# design.net
KiCad netlist of a schematic drawn in EAGLE
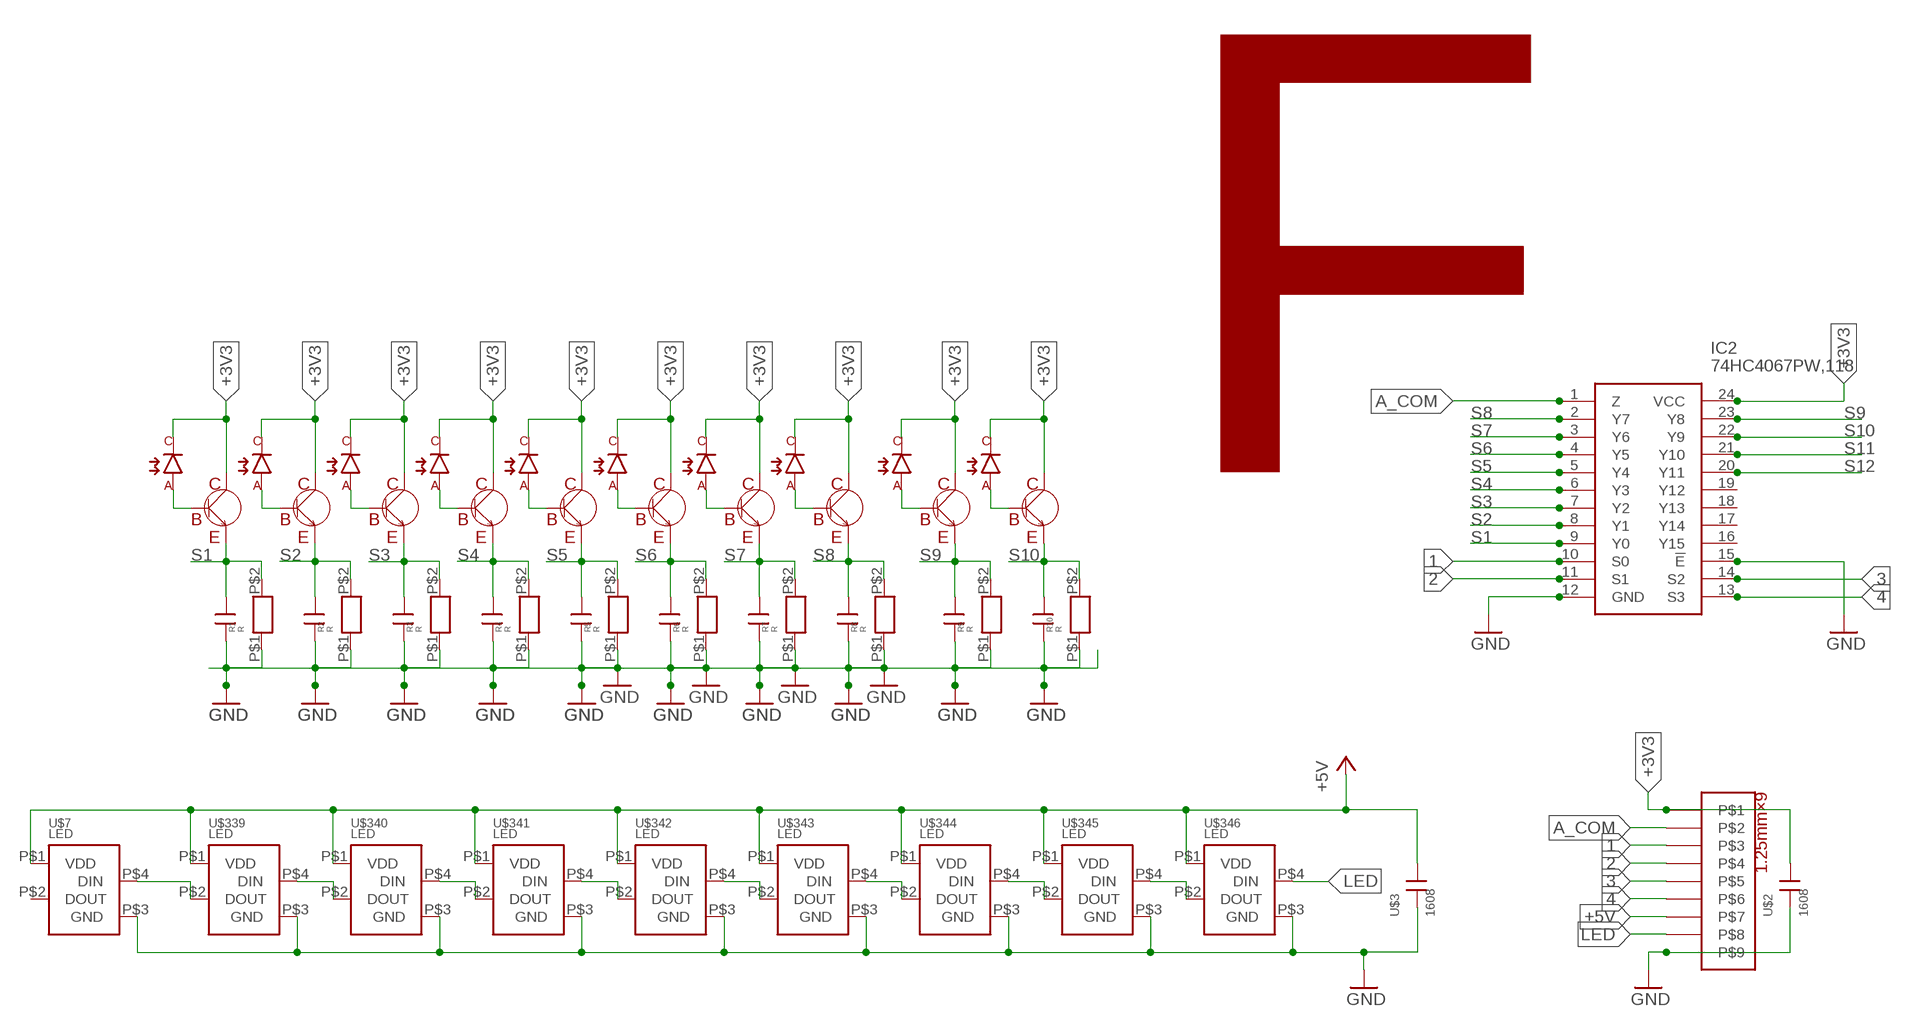
[diagram p0: schematic, sheet 2]

(export (version "E")
  (design (tool "Eeschema 10.0.6"))
  (components
    (comp (ref "C1")
      (value "1608")
      (footprint "eagle-import:CON")
      (libsource (lib "eagle-import") (part "1608"))
    )
    (comp (ref "C2")
      (value "1608")
      (footprint "eagle-import:CON")
      (libsource (lib "eagle-import") (part "1608"))
    )
    (comp (ref "C3")
      (value "1608")
      (footprint "eagle-import:CON")
      (libsource (lib "eagle-import") (part "1608"))
    )
    (comp (ref "C4")
      (value "1608")
      (footprint "eagle-import:CON")
      (libsource (lib "eagle-import") (part "1608"))
    )
    (comp (ref "C5")
      (value "1608")
      (footprint "eagle-import:CON")
      (libsource (lib "eagle-import") (part "1608"))
    )
    (comp (ref "C6")
      (value "1608")
      (footprint "eagle-import:CON")
      (libsource (lib "eagle-import") (part "1608"))
    )
    (comp (ref "C7")
      (value "1608")
      (footprint "eagle-import:CON")
      (libsource (lib "eagle-import") (part "1608"))
    )
    (comp (ref "C8")
      (value "1608")
      (footprint "eagle-import:CON")
      (libsource (lib "eagle-import") (part "1608"))
    )
    (comp (ref "C9")
      (value "1608")
      (footprint "eagle-import:CON")
      (libsource (lib "eagle-import") (part "1608"))
    )
    (comp (ref "C10")
      (value "1608")
      (footprint "eagle-import:CON")
      (libsource (lib "eagle-import") (part "1608"))
    )
    (comp (ref "IC2")
      (value "74HC4067PW,118")
      (footprint "eagle-import:SOP65P640X110-24N")
      (fields (field (name "MOUSER_PART_NUMBER") "771-74HC4067PW-T"))
      (libsource (lib "eagle-import") (part "74HC4067PW,118"))
    )
    (comp (ref "R1") (value "R") (footprint "eagle-import:1608") (libsource (lib "eagle-import") (part "R")))
    (comp (ref "R2") (value "R") (footprint "eagle-import:1608") (libsource (lib "eagle-import") (part "R")))
    (comp (ref "R3") (value "R") (footprint "eagle-import:1608") (libsource (lib "eagle-import") (part "R")))
    (comp (ref "R4") (value "R") (footprint "eagle-import:1608") (libsource (lib "eagle-import") (part "R")))
    (comp (ref "R5") (value "R") (footprint "eagle-import:1608") (libsource (lib "eagle-import") (part "R")))
    (comp (ref "R6") (value "R") (footprint "eagle-import:1608") (libsource (lib "eagle-import") (part "R")))
    (comp (ref "R7") (value "R") (footprint "eagle-import:1608") (libsource (lib "eagle-import") (part "R")))
    (comp (ref "R8") (value "R") (footprint "eagle-import:1608") (libsource (lib "eagle-import") (part "R")))
    (comp (ref "R9") (value "R") (footprint "eagle-import:1608") (libsource (lib "eagle-import") (part "R")))
    (comp (ref "R10") (value "R") (footprint "eagle-import:1608") (libsource (lib "eagle-import") (part "R")))
    (comp (ref "U$1")
      (value "1MMCON")
      (footprint "eagle-import:1MMCON")
      (libsource (lib "eagle-import") (part "1MMCON"))
    )
    (comp (ref "U$2")
      (value "1608")
      (footprint "eagle-import:CON")
      (libsource (lib "eagle-import") (part "1608"))
    )
    (comp (ref "U$3")
      (value "1608")
      (footprint "eagle-import:CON")
      (libsource (lib "eagle-import") (part "1608"))
    )
    (comp (ref "U$7")
      (value "LED")
      (footprint "eagle-import:LED")
      (libsource (lib "eagle-import") (part "LED"))
    )
    (comp (ref "U$17")
      (value "2CS2712")
      (footprint "eagle-import:TRANS_SSM3J325F,LF")
      (libsource (lib "eagle-import") (part "2CS2712"))
    )
    (comp (ref "U$18")
      (value "フォトダイオード")
      (footprint "eagle-import:フォトダイオード")
      (libsource (lib "eagle-import") (part "フォトダイオード"))
    )
    (comp (ref "U$19")
      (value "2CS2712")
      (footprint "eagle-import:TRANS_SSM3J325F,LF")
      (libsource (lib "eagle-import") (part "2CS2712"))
    )
    (comp (ref "U$20")
      (value "フォトダイオード")
      (footprint "eagle-import:フォトダイオード")
      (libsource (lib "eagle-import") (part "フォトダイオード"))
    )
    (comp (ref "U$21")
      (value "2CS2712")
      (footprint "eagle-import:TRANS_SSM3J325F,LF")
      (libsource (lib "eagle-import") (part "2CS2712"))
    )
    (comp (ref "U$22")
      (value "フォトダイオード")
      (footprint "eagle-import:フォトダイオード")
      (libsource (lib "eagle-import") (part "フォトダイオード"))
    )
    (comp (ref "U$23")
      (value "2CS2712")
      (footprint "eagle-import:TRANS_SSM3J325F,LF")
      (libsource (lib "eagle-import") (part "2CS2712"))
    )
    (comp (ref "U$24")
      (value "フォトダイオード")
      (footprint "eagle-import:フォトダイオード")
      (libsource (lib "eagle-import") (part "フォトダイオード"))
    )
    (comp (ref "U$25")
      (value "2CS2712")
      (footprint "eagle-import:TRANS_SSM3J325F,LF")
      (libsource (lib "eagle-import") (part "2CS2712"))
    )
    (comp (ref "U$26")
      (value "フォトダイオード")
      (footprint "eagle-import:フォトダイオード")
      (libsource (lib "eagle-import") (part "フォトダイオード"))
    )
    (comp (ref "U$27")
      (value "2CS2712")
      (footprint "eagle-import:TRANS_SSM3J325F,LF")
      (libsource (lib "eagle-import") (part "2CS2712"))
    )
    (comp (ref "U$28")
      (value "フォトダイオード")
      (footprint "eagle-import:フォトダイオード")
      (libsource (lib "eagle-import") (part "フォトダイオード"))
    )
    (comp (ref "U$29")
      (value "2CS2712")
      (footprint "eagle-import:TRANS_SSM3J325F,LF")
      (libsource (lib "eagle-import") (part "2CS2712"))
    )
    (comp (ref "U$30")
      (value "フォトダイオード")
      (footprint "eagle-import:フォトダイオード")
      (libsource (lib "eagle-import") (part "フォトダイオード"))
    )
    (comp (ref "U$31")
      (value "2CS2712")
      (footprint "eagle-import:TRANS_SSM3J325F,LF")
      (libsource (lib "eagle-import") (part "2CS2712"))
    )
    (comp (ref "U$32")
      (value "フォトダイオード")
      (footprint "eagle-import:フォトダイオード")
      (libsource (lib "eagle-import") (part "フォトダイオード"))
    )
    (comp (ref "U$53")
      (value "2CS2712")
      (footprint "eagle-import:TRANS_SSM3J325F,LF")
      (libsource (lib "eagle-import") (part "2CS2712"))
    )
    (comp (ref "U$54")
      (value "フォトダイオード")
      (footprint "eagle-import:フォトダイオード")
      (libsource (lib "eagle-import") (part "フォトダイオード"))
    )
    (comp (ref "U$55")
      (value "2CS2712")
      (footprint "eagle-import:TRANS_SSM3J325F,LF")
      (libsource (lib "eagle-import") (part "2CS2712"))
    )
    (comp (ref "U$56")
      (value "フォトダイオード")
      (footprint "eagle-import:フォトダイオード")
      (libsource (lib "eagle-import") (part "フォトダイオード"))
    )
    (comp (ref "U$339")
      (value "LED")
      (footprint "eagle-import:LED")
      (libsource (lib "eagle-import") (part "LED"))
    )
    (comp (ref "U$340")
      (value "LED")
      (footprint "eagle-import:LED")
      (libsource (lib "eagle-import") (part "LED"))
    )
    (comp (ref "U$341")
      (value "LED")
      (footprint "eagle-import:LED")
      (libsource (lib "eagle-import") (part "LED"))
    )
    (comp (ref "U$342")
      (value "LED")
      (footprint "eagle-import:LED")
      (libsource (lib "eagle-import") (part "LED"))
    )
    (comp (ref "U$343")
      (value "LED")
      (footprint "eagle-import:LED")
      (libsource (lib "eagle-import") (part "LED"))
    )
    (comp (ref "U$344")
      (value "LED")
      (footprint "eagle-import:LED")
      (libsource (lib "eagle-import") (part "LED"))
    )
    (comp (ref "U$345")
      (value "LED")
      (footprint "eagle-import:LED")
      (libsource (lib "eagle-import") (part "LED"))
    )
    (comp (ref "U$346")
      (value "LED")
      (footprint "eagle-import:LED")
      (libsource (lib "eagle-import") (part "LED"))
    )
  )
  (nets
    (net (code "1") (name "+3V3") (class "Default")
      (node (ref "IC2") (pin "24") (pinfunction "VCC_24") (pintype "bidirectional"))
      (node (ref "U$1") (pin "P$1") (pinfunction "P$1_P$1") (pintype "bidirectional"))
      (node (ref "U$17") (pin "C") (pinfunction "C_C") (pintype "bidirectional"))
      (node (ref "U$18") (pin "C") (pinfunction "C_C") (pintype "bidirectional"))
      (node (ref "U$19") (pin "C") (pinfunction "C_C") (pintype "bidirectional"))
      (node (ref "U$2") (pin "P$1") (pinfunction "1_P$1") (pintype "bidirectional"))
      (node (ref "U$20") (pin "C") (pinfunction "C_C") (pintype "bidirectional"))
      (node (ref "U$21") (pin "C") (pinfunction "C_C") (pintype "bidirectional"))
      (node (ref "U$22") (pin "C") (pinfunction "C_C") (pintype "bidirectional"))
      (node (ref "U$23") (pin "C") (pinfunction "C_C") (pintype "bidirectional"))
      (node (ref "U$24") (pin "C") (pinfunction "C_C") (pintype "bidirectional"))
      (node (ref "U$25") (pin "C") (pinfunction "C_C") (pintype "bidirectional"))
      (node (ref "U$26") (pin "C") (pinfunction "C_C") (pintype "bidirectional"))
      (node (ref "U$27") (pin "C") (pinfunction "C_C") (pintype "bidirectional"))
      (node (ref "U$28") (pin "C") (pinfunction "C_C") (pintype "bidirectional"))
      (node (ref "U$29") (pin "C") (pinfunction "C_C") (pintype "bidirectional"))
      (node (ref "U$30") (pin "C") (pinfunction "C_C") (pintype "bidirectional"))
      (node (ref "U$31") (pin "C") (pinfunction "C_C") (pintype "bidirectional"))
      (node (ref "U$32") (pin "C") (pinfunction "C_C") (pintype "bidirectional"))
      (node (ref "U$53") (pin "C") (pinfunction "C_C") (pintype "bidirectional"))
      (node (ref "U$54") (pin "C") (pinfunction "C_C") (pintype "bidirectional"))
      (node (ref "U$55") (pin "C") (pinfunction "C_C") (pintype "bidirectional"))
      (node (ref "U$56") (pin "C") (pinfunction "C_C") (pintype "bidirectional"))
    )
    (net (code "2") (name "+5V") (class "Default")
      (node (ref "U$1") (pin "P$7") (pinfunction "P$7_P$7") (pintype "bidirectional"))
      (node (ref "U$3") (pin "P$1") (pinfunction "1_P$1") (pintype "bidirectional"))
      (node (ref "U$339") (pin "P$1") (pinfunction "VDD_P$1") (pintype "bidirectional"))
      (node (ref "U$340") (pin "P$1") (pinfunction "VDD_P$1") (pintype "bidirectional"))
      (node (ref "U$341") (pin "P$1") (pinfunction "VDD_P$1") (pintype "bidirectional"))
      (node (ref "U$342") (pin "P$1") (pinfunction "VDD_P$1") (pintype "bidirectional"))
      (node (ref "U$343") (pin "P$1") (pinfunction "VDD_P$1") (pintype "bidirectional"))
      (node (ref "U$344") (pin "P$1") (pinfunction "VDD_P$1") (pintype "bidirectional"))
      (node (ref "U$345") (pin "P$1") (pinfunction "VDD_P$1") (pintype "bidirectional"))
      (node (ref "U$346") (pin "P$1") (pinfunction "VDD_P$1") (pintype "bidirectional"))
      (node (ref "U$7") (pin "P$1") (pinfunction "VDD_P$1") (pintype "bidirectional"))
    )
    (net (code "3") (name "1") (class "Default")
      (node (ref "IC2") (pin "10") (pinfunction "S0_10") (pintype "bidirectional"))
      (node (ref "U$1") (pin "P$3") (pinfunction "P$3_P$3") (pintype "bidirectional"))
    )
    (net (code "4") (name "2") (class "Default")
      (node (ref "IC2") (pin "11") (pinfunction "S1_11") (pintype "bidirectional"))
      (node (ref "U$1") (pin "P$4") (pinfunction "P$4_P$4") (pintype "bidirectional"))
    )
    (net (code "5") (name "3") (class "Default")
      (node (ref "IC2") (pin "14") (pinfunction "S2_14") (pintype "bidirectional"))
      (node (ref "U$1") (pin "P$5") (pinfunction "P$5_P$5") (pintype "bidirectional"))
    )
    (net (code "6") (name "4") (class "Default")
      (node (ref "IC2") (pin "13") (pinfunction "S3_13") (pintype "bidirectional"))
      (node (ref "U$1") (pin "P$6") (pinfunction "P$6_P$6") (pintype "bidirectional"))
    )
    (net (code "7") (name "A_COM") (class "Default")
      (node (ref "IC2") (pin "1") (pinfunction "Z_1") (pintype "bidirectional"))
      (node (ref "U$1") (pin "P$2") (pinfunction "P$2_P$2") (pintype "bidirectional"))
    )
    (net (code "8") (name "GND") (class "Default")
      (node (ref "C1") (pin "P$2") (pinfunction "2_P$2") (pintype "bidirectional"))
      (node (ref "C10") (pin "P$2") (pinfunction "2_P$2") (pintype "bidirectional"))
      (node (ref "C2") (pin "P$2") (pinfunction "2_P$2") (pintype "bidirectional"))
      (node (ref "C3") (pin "P$2") (pinfunction "2_P$2") (pintype "bidirectional"))
      (node (ref "C4") (pin "P$2") (pinfunction "2_P$2") (pintype "bidirectional"))
      (node (ref "C5") (pin "P$2") (pinfunction "2_P$2") (pintype "bidirectional"))
      (node (ref "C6") (pin "P$2") (pinfunction "2_P$2") (pintype "bidirectional"))
      (node (ref "C7") (pin "P$2") (pinfunction "2_P$2") (pintype "bidirectional"))
      (node (ref "C8") (pin "P$2") (pinfunction "2_P$2") (pintype "bidirectional"))
      (node (ref "C9") (pin "P$2") (pinfunction "2_P$2") (pintype "bidirectional"))
      (node (ref "IC2") (pin "12") (pinfunction "GND_12") (pintype "bidirectional"))
      (node (ref "IC2") (pin "15") (pinfunction "~{E}_15") (pintype "bidirectional"))
      (node (ref "R1") (pin "P$1") (pinfunction "P$1_P$1") (pintype "bidirectional"))
      (node (ref "R10") (pin "P$1") (pinfunction "P$1_P$1") (pintype "bidirectional"))
      (node (ref "R2") (pin "P$1") (pinfunction "P$1_P$1") (pintype "bidirectional"))
      (node (ref "R3") (pin "P$1") (pinfunction "P$1_P$1") (pintype "bidirectional"))
      (node (ref "R4") (pin "P$1") (pinfunction "P$1_P$1") (pintype "bidirectional"))
      (node (ref "R5") (pin "P$1") (pinfunction "P$1_P$1") (pintype "bidirectional"))
      (node (ref "R6") (pin "P$1") (pinfunction "P$1_P$1") (pintype "bidirectional"))
      (node (ref "R7") (pin "P$1") (pinfunction "P$1_P$1") (pintype "bidirectional"))
      (node (ref "R8") (pin "P$1") (pinfunction "P$1_P$1") (pintype "bidirectional"))
      (node (ref "R9") (pin "P$1") (pinfunction "P$1_P$1") (pintype "bidirectional"))
      (node (ref "U$1") (pin "P$9") (pinfunction "P$9_P$9") (pintype "bidirectional"))
      (node (ref "U$2") (pin "P$2") (pinfunction "2_P$2") (pintype "bidirectional"))
      (node (ref "U$3") (pin "P$2") (pinfunction "2_P$2") (pintype "bidirectional"))
      (node (ref "U$339") (pin "P$3") (pinfunction "GND_P$3") (pintype "bidirectional"))
      (node (ref "U$340") (pin "P$3") (pinfunction "GND_P$3") (pintype "bidirectional"))
      (node (ref "U$341") (pin "P$3") (pinfunction "GND_P$3") (pintype "bidirectional"))
      (node (ref "U$342") (pin "P$3") (pinfunction "GND_P$3") (pintype "bidirectional"))
      (node (ref "U$343") (pin "P$3") (pinfunction "GND_P$3") (pintype "bidirectional"))
      (node (ref "U$344") (pin "P$3") (pinfunction "GND_P$3") (pintype "bidirectional"))
      (node (ref "U$345") (pin "P$3") (pinfunction "GND_P$3") (pintype "bidirectional"))
      (node (ref "U$346") (pin "P$3") (pinfunction "GND_P$3") (pintype "bidirectional"))
      (node (ref "U$7") (pin "P$3") (pinfunction "GND_P$3") (pintype "bidirectional"))
    )
    (net (code "9") (name "LED") (class "Default")
      (node (ref "U$1") (pin "P$8") (pinfunction "P$8_P$8") (pintype "bidirectional"))
      (node (ref "U$346") (pin "P$4") (pinfunction "DIN_P$4") (pintype "bidirectional"))
    )
    (net (code "10") (name "Net-(U$17-PadB)") (class "Default")
      (node (ref "U$17") (pin "B") (pinfunction "B_B") (pintype "bidirectional"))
      (node (ref "U$18") (pin "A") (pinfunction "A_A") (pintype "bidirectional"))
    )
    (net (code "11") (name "Net-(U$19-PadB)") (class "Default")
      (node (ref "U$19") (pin "B") (pinfunction "B_B") (pintype "bidirectional"))
      (node (ref "U$20") (pin "A") (pinfunction "A_A") (pintype "bidirectional"))
    )
    (net (code "12") (name "Net-(U$21-PadB)") (class "Default")
      (node (ref "U$21") (pin "B") (pinfunction "B_B") (pintype "bidirectional"))
      (node (ref "U$22") (pin "A") (pinfunction "A_A") (pintype "bidirectional"))
    )
    (net (code "13") (name "Net-(U$23-PadB)") (class "Default")
      (node (ref "U$23") (pin "B") (pinfunction "B_B") (pintype "bidirectional"))
      (node (ref "U$24") (pin "A") (pinfunction "A_A") (pintype "bidirectional"))
    )
    (net (code "14") (name "Net-(U$25-PadB)") (class "Default")
      (node (ref "U$25") (pin "B") (pinfunction "B_B") (pintype "bidirectional"))
      (node (ref "U$26") (pin "A") (pinfunction "A_A") (pintype "bidirectional"))
    )
    (net (code "15") (name "Net-(U$27-PadB)") (class "Default")
      (node (ref "U$27") (pin "B") (pinfunction "B_B") (pintype "bidirectional"))
      (node (ref "U$28") (pin "A") (pinfunction "A_A") (pintype "bidirectional"))
    )
    (net (code "16") (name "Net-(U$29-PadB)") (class "Default")
      (node (ref "U$29") (pin "B") (pinfunction "B_B") (pintype "bidirectional"))
      (node (ref "U$30") (pin "A") (pinfunction "A_A") (pintype "bidirectional"))
    )
    (net (code "17") (name "Net-(U$31-PadB)") (class "Default")
      (node (ref "U$31") (pin "B") (pinfunction "B_B") (pintype "bidirectional"))
      (node (ref "U$32") (pin "A") (pinfunction "A_A") (pintype "bidirectional"))
    )
    (net (code "18") (name "Net-(U$53-PadB)") (class "Default")
      (node (ref "U$53") (pin "B") (pinfunction "B_B") (pintype "bidirectional"))
      (node (ref "U$54") (pin "A") (pinfunction "A_A") (pintype "bidirectional"))
    )
    (net (code "19") (name "Net-(U$55-PadB)") (class "Default")
      (node (ref "U$55") (pin "B") (pinfunction "B_B") (pintype "bidirectional"))
      (node (ref "U$56") (pin "A") (pinfunction "A_A") (pintype "bidirectional"))
    )
    (net (code "20") (name "Net-(U$339-DIN)") (class "Default")
      (node (ref "U$339") (pin "P$4") (pinfunction "DIN_P$4") (pintype "bidirectional"))
      (node (ref "U$340") (pin "P$2") (pinfunction "DOUT_P$2") (pintype "bidirectional"))
    )
    (net (code "21") (name "Net-(U$339-DOUT)") (class "Default")
      (node (ref "U$339") (pin "P$2") (pinfunction "DOUT_P$2") (pintype "bidirectional"))
      (node (ref "U$7") (pin "P$4") (pinfunction "DIN_P$4") (pintype "bidirectional"))
    )
    (net (code "22") (name "Net-(U$340-DIN)") (class "Default")
      (node (ref "U$340") (pin "P$4") (pinfunction "DIN_P$4") (pintype "bidirectional"))
      (node (ref "U$341") (pin "P$2") (pinfunction "DOUT_P$2") (pintype "bidirectional"))
    )
    (net (code "23") (name "Net-(U$341-DIN)") (class "Default")
      (node (ref "U$341") (pin "P$4") (pinfunction "DIN_P$4") (pintype "bidirectional"))
      (node (ref "U$342") (pin "P$2") (pinfunction "DOUT_P$2") (pintype "bidirectional"))
    )
    (net (code "24") (name "Net-(U$342-DIN)") (class "Default")
      (node (ref "U$342") (pin "P$4") (pinfunction "DIN_P$4") (pintype "bidirectional"))
      (node (ref "U$343") (pin "P$2") (pinfunction "DOUT_P$2") (pintype "bidirectional"))
    )
    (net (code "25") (name "Net-(U$343-DIN)") (class "Default")
      (node (ref "U$343") (pin "P$4") (pinfunction "DIN_P$4") (pintype "bidirectional"))
      (node (ref "U$344") (pin "P$2") (pinfunction "DOUT_P$2") (pintype "bidirectional"))
    )
    (net (code "26") (name "Net-(U$344-DIN)") (class "Default")
      (node (ref "U$344") (pin "P$4") (pinfunction "DIN_P$4") (pintype "bidirectional"))
      (node (ref "U$345") (pin "P$2") (pinfunction "DOUT_P$2") (pintype "bidirectional"))
    )
    (net (code "27") (name "Net-(U$345-DIN)") (class "Default")
      (node (ref "U$345") (pin "P$4") (pinfunction "DIN_P$4") (pintype "bidirectional"))
      (node (ref "U$346") (pin "P$2") (pinfunction "DOUT_P$2") (pintype "bidirectional"))
    )
    (net (code "28") (name "S1") (class "Default")
      (node (ref "C1") (pin "P$1") (pinfunction "1_P$1") (pintype "bidirectional"))
      (node (ref "IC2") (pin "9") (pinfunction "Y0_9") (pintype "bidirectional"))
      (node (ref "R1") (pin "P$2") (pinfunction "P$2_P$2") (pintype "bidirectional"))
      (node (ref "U$17") (pin "E") (pinfunction "E_E") (pintype "bidirectional"))
    )
    (net (code "29") (name "S2") (class "Default")
      (node (ref "C2") (pin "P$1") (pinfunction "1_P$1") (pintype "bidirectional"))
      (node (ref "IC2") (pin "8") (pinfunction "Y1_8") (pintype "bidirectional"))
      (node (ref "R2") (pin "P$2") (pinfunction "P$2_P$2") (pintype "bidirectional"))
      (node (ref "U$19") (pin "E") (pinfunction "E_E") (pintype "bidirectional"))
    )
    (net (code "30") (name "S3") (class "Default")
      (node (ref "C3") (pin "P$1") (pinfunction "1_P$1") (pintype "bidirectional"))
      (node (ref "IC2") (pin "7") (pinfunction "Y2_7") (pintype "bidirectional"))
      (node (ref "R3") (pin "P$2") (pinfunction "P$2_P$2") (pintype "bidirectional"))
      (node (ref "U$21") (pin "E") (pinfunction "E_E") (pintype "bidirectional"))
    )
    (net (code "31") (name "S4") (class "Default")
      (node (ref "C4") (pin "P$1") (pinfunction "1_P$1") (pintype "bidirectional"))
      (node (ref "IC2") (pin "6") (pinfunction "Y3_6") (pintype "bidirectional"))
      (node (ref "R4") (pin "P$2") (pinfunction "P$2_P$2") (pintype "bidirectional"))
      (node (ref "U$23") (pin "E") (pinfunction "E_E") (pintype "bidirectional"))
    )
    (net (code "32") (name "S5") (class "Default")
      (node (ref "C5") (pin "P$1") (pinfunction "1_P$1") (pintype "bidirectional"))
      (node (ref "IC2") (pin "5") (pinfunction "Y4_5") (pintype "bidirectional"))
      (node (ref "R5") (pin "P$2") (pinfunction "P$2_P$2") (pintype "bidirectional"))
      (node (ref "U$25") (pin "E") (pinfunction "E_E") (pintype "bidirectional"))
    )
    (net (code "33") (name "S6") (class "Default")
      (node (ref "C6") (pin "P$1") (pinfunction "1_P$1") (pintype "bidirectional"))
      (node (ref "IC2") (pin "4") (pinfunction "Y5_4") (pintype "bidirectional"))
      (node (ref "R6") (pin "P$2") (pinfunction "P$2_P$2") (pintype "bidirectional"))
      (node (ref "U$27") (pin "E") (pinfunction "E_E") (pintype "bidirectional"))
    )
    (net (code "34") (name "S7") (class "Default")
      (node (ref "C7") (pin "P$1") (pinfunction "1_P$1") (pintype "bidirectional"))
      (node (ref "IC2") (pin "3") (pinfunction "Y6_3") (pintype "bidirectional"))
      (node (ref "R7") (pin "P$2") (pinfunction "P$2_P$2") (pintype "bidirectional"))
      (node (ref "U$29") (pin "E") (pinfunction "E_E") (pintype "bidirectional"))
    )
    (net (code "35") (name "S8") (class "Default")
      (node (ref "C8") (pin "P$1") (pinfunction "1_P$1") (pintype "bidirectional"))
      (node (ref "IC2") (pin "2") (pinfunction "Y7_2") (pintype "bidirectional"))
      (node (ref "R8") (pin "P$2") (pinfunction "P$2_P$2") (pintype "bidirectional"))
      (node (ref "U$31") (pin "E") (pinfunction "E_E") (pintype "bidirectional"))
    )
    (net (code "36") (name "S9") (class "Default")
      (node (ref "C9") (pin "P$1") (pinfunction "1_P$1") (pintype "bidirectional"))
      (node (ref "IC2") (pin "23") (pinfunction "Y8_23") (pintype "bidirectional"))
      (node (ref "R9") (pin "P$2") (pinfunction "P$2_P$2") (pintype "bidirectional"))
      (node (ref "U$53") (pin "E") (pinfunction "E_E") (pintype "bidirectional"))
    )
    (net (code "37") (name "S10") (class "Default")
      (node (ref "C10") (pin "P$1") (pinfunction "1_P$1") (pintype "bidirectional"))
      (node (ref "IC2") (pin "22") (pinfunction "Y9_22") (pintype "bidirectional"))
      (node (ref "R10") (pin "P$2") (pinfunction "P$2_P$2") (pintype "bidirectional"))
      (node (ref "U$55") (pin "E") (pinfunction "E_E") (pintype "bidirectional"))
    )
    (net (code "38") (name "S11") (class "Default")
      (node (ref "IC2") (pin "21") (pinfunction "Y10_21") (pintype "bidirectional"))
    )
    (net (code "39") (name "S12") (class "Default")
      (node (ref "IC2") (pin "20") (pinfunction "Y11_20") (pintype "bidirectional"))
    )
    (net (code "40") (name "unconnected-(IC2-Y12-Pad19)") (class "Default")
      (node (ref "IC2") (pin "19") (pinfunction "Y12_19") (pintype "bidirectional"))
    )
    (net (code "41") (name "unconnected-(IC2-Y13-Pad18)") (class "Default")
      (node (ref "IC2") (pin "18") (pinfunction "Y13_18") (pintype "bidirectional"))
    )
    (net (code "42") (name "unconnected-(IC2-Y14-Pad17)") (class "Default")
      (node (ref "IC2") (pin "17") (pinfunction "Y14_17") (pintype "bidirectional"))
    )
    (net (code "43") (name "unconnected-(IC2-Y15-Pad16)") (class "Default")
      (node (ref "IC2") (pin "16") (pinfunction "Y15_16") (pintype "bidirectional"))
    )
    (net (code "44") (name "unconnected-(U$7-DOUT-PadP$2)") (class "Default")
      (node (ref "U$7") (pin "P$2") (pinfunction "DOUT_P$2") (pintype "bidirectional"))
    )
  )
)
